# Processor.net
KiCad netlist of a schematic drawn in Altium Designer
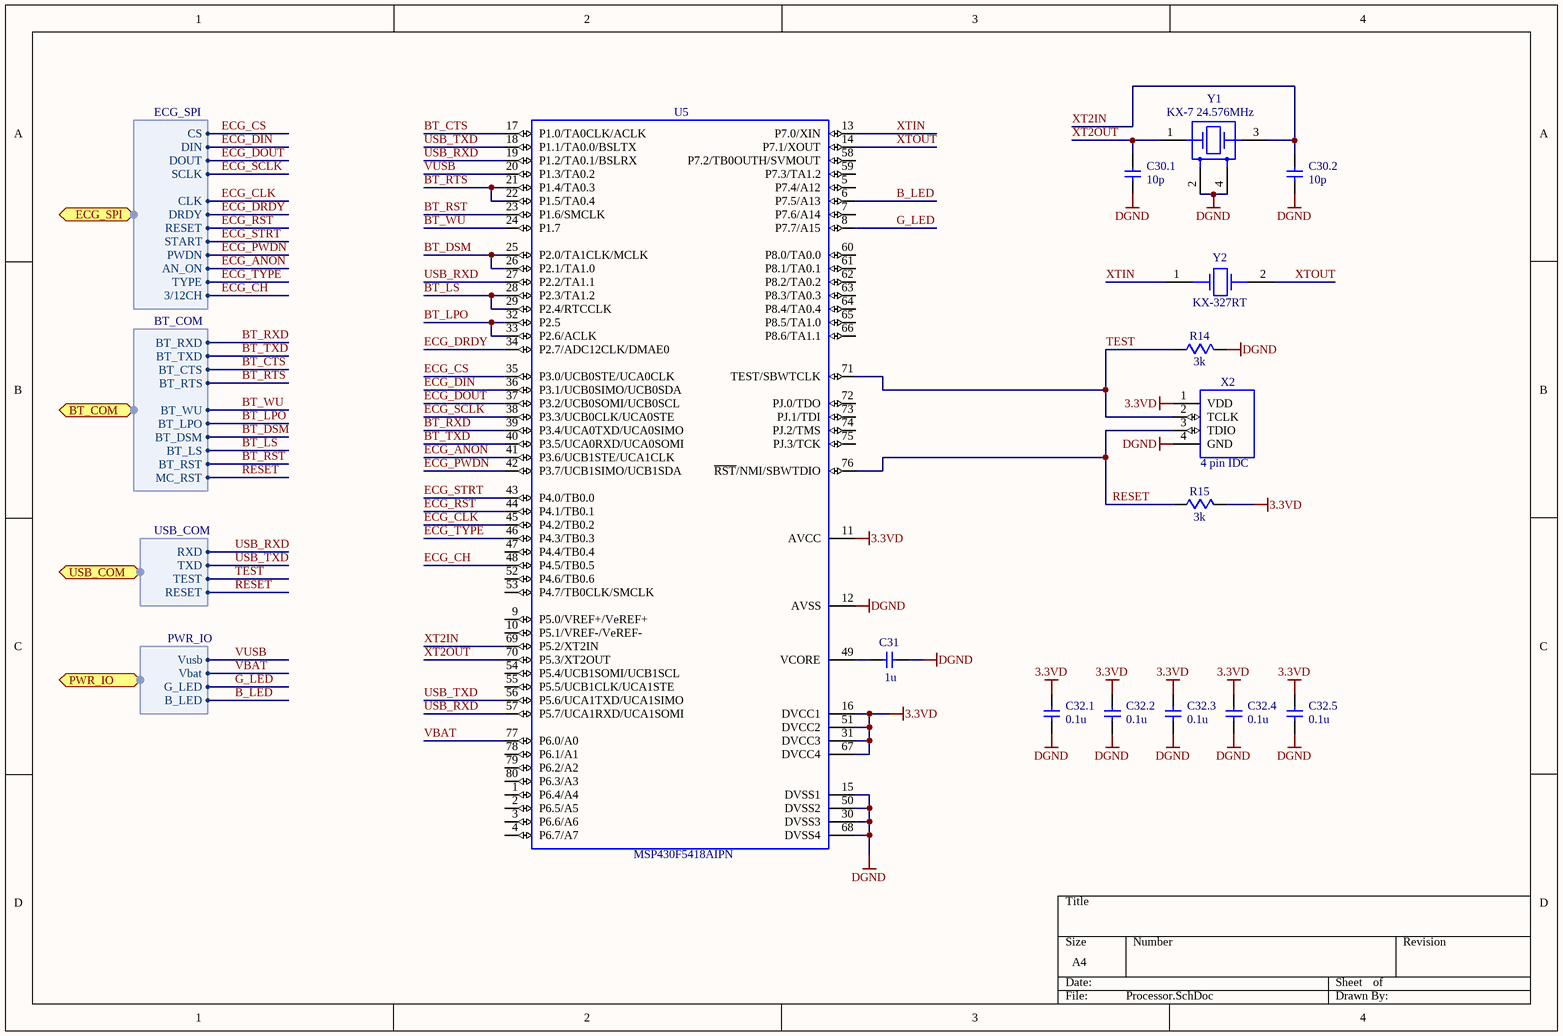
[diagram p0: Processor.SchDoc]

(export (version "E")
  (design (tool "Eeschema 10.0.6"))
  (components
    (comp (ref "C30.1") (value "10p") (footprint "SMD/C/0603") (libsource (lib "My_lib") (part "Capacitor")))
    (comp (ref "C30.2") (value "10p") (footprint "SMD/C/0603") (libsource (lib "My_lib") (part "Capacitor")))
    (comp (ref "C31") (value "1u") (footprint "SMD/C/0603") (libsource (lib "My_lib") (part "Capacitor")))
    (comp (ref "C32.1") (value "0.1u") (footprint "SMD/C/0603") (libsource (lib "My_lib") (part "Capacitor")))
    (comp (ref "C32.2") (value "0.1u") (footprint "SMD/C/0603") (libsource (lib "My_lib") (part "Capacitor")))
    (comp (ref "C32.3") (value "0.1u") (footprint "SMD/C/0603") (libsource (lib "My_lib") (part "Capacitor")))
    (comp (ref "C32.4") (value "0.1u") (footprint "SMD/C/0603") (libsource (lib "My_lib") (part "Capacitor")))
    (comp (ref "C32.5") (value "0.1u") (footprint "SMD/C/0603") (libsource (lib "My_lib") (part "Capacitor")))
    (comp (ref "R14") (value "3k") (footprint "SMD/R/0603") (libsource (lib "My_lib") (part "Resistor")))
    (comp (ref "R15") (value "3k") (footprint "SMD/R/0603") (libsource (lib "My_lib") (part "Resistor")))
    (comp (ref "U5")
      (value "MSP430F5418AIPN")
      (footprint "SMD/QFP80/0.5MMP/12x12MM/14X14MMWP")
      (description "Mixed Signal Microcontroller")
      (libsource (lib "My_lib") (part "MSP430F5418AIPN"))
    )
    (comp (ref "X2")
      (value "4 pin IDC")
      (footprint "CONNECTOR/IDC/0.05P/1X4")
      (description "MSP430 JTAG Connector")
      (libsource (lib "My_lib") (part "MSP430 JTAG SBW"))
    )
    (comp (ref "Y1")
      (value "KX-7 24.576MHz")
      (footprint "KX-7")
      (description "Quartz Crystal")
      (libsource (lib "My_lib") (part "KX-9A"))
    )
    (comp (ref "Y2")
      (value "KX-327RT")
      (footprint "KX–327RT")
      (description "Quartz Crystal")
      (libsource (lib "My_lib") (part "KX-327RT"))
    )
  )
  (nets
    (net (code "5") (name "/BT_CTS") (class "Default")
      (node (ref "U5") (pin "17") (pinfunction "P1.0/TA0CLK/ACLK_17") (pintype "bidirectional"))
    )
    (net (code "6") (name "/BT_DSM") (class "Default")
      (node (ref "U5") (pin "25") (pinfunction "P2.0/TA1CLK/MCLK_25") (pintype "bidirectional"))
      (node (ref "U5") (pin "26") (pinfunction "P2.1/TA1.0_26") (pintype "bidirectional"))
    )
    (net (code "7") (name "/BT_LPO") (class "Default")
      (node (ref "U5") (pin "32") (pinfunction "P2.5_32") (pintype "bidirectional"))
      (node (ref "U5") (pin "33") (pinfunction "P2.6/ACLK_33") (pintype "bidirectional"))
    )
    (net (code "8") (name "/BT_LS") (class "Default")
      (node (ref "U5") (pin "28") (pinfunction "P2.3/TA1.2_28") (pintype "bidirectional"))
      (node (ref "U5") (pin "29") (pinfunction "P2.4/RTCCLK_29") (pintype "bidirectional"))
    )
    (net (code "9") (name "/BT_RST") (class "Default")
      (node (ref "U5") (pin "23") (pinfunction "P1.6/SMCLK_23") (pintype "bidirectional"))
    )
    (net (code "10") (name "/BT_RTS") (class "Default")
      (node (ref "U5") (pin "21") (pinfunction "P1.4/TA0.3_21") (pintype "bidirectional"))
      (node (ref "U5") (pin "22") (pinfunction "P1.5/TA0.4_22") (pintype "bidirectional"))
    )
    (net (code "11") (name "/BT_RXD") (class "Default")
      (node (ref "U5") (pin "39") (pinfunction "P3.4/UCA0TXD/UCA0SIMO_39") (pintype "bidirectional"))
    )
    (net (code "12") (name "/BT_TXD") (class "Default")
      (node (ref "U5") (pin "40") (pinfunction "P3.5/UCA0RXD/UCA0SOMI_40") (pintype "bidirectional"))
    )
    (net (code "13") (name "/BT_WU") (class "Default")
      (node (ref "U5") (pin "24") (pinfunction "P1.7_24") (pintype "bidirectional"))
    )
    (net (code "14") (name "/B_LED") (class "Default")
      (node (ref "U5") (pin "6") (pinfunction "P7.5/A13_6") (pintype "bidirectional"))
    )
    (net (code "15") (name "/ECG_ANON") (class "Default")
      (node (ref "U5") (pin "41") (pinfunction "P3.6/UCB1STE/UCA1CLK_41") (pintype "bidirectional"))
    )
    (net (code "16") (name "/ECG_CH") (class "Default")
      (node (ref "U5") (pin "48") (pinfunction "P4.5/TB0.5_48") (pintype "bidirectional"))
    )
    (net (code "17") (name "/ECG_CLK") (class "Default")
      (node (ref "U5") (pin "45") (pinfunction "P4.2/TB0.2_45") (pintype "bidirectional"))
    )
    (net (code "18") (name "/ECG_CS") (class "Default")
      (node (ref "U5") (pin "35") (pinfunction "P3.0/UCB0STE/UCA0CLK_35") (pintype "bidirectional"))
    )
    (net (code "19") (name "/ECG_DIN") (class "Default")
      (node (ref "U5") (pin "36") (pinfunction "P3.1/UCB0SIMO/UCB0SDA_36") (pintype "bidirectional"))
    )
    (net (code "20") (name "/ECG_DOUT") (class "Default")
      (node (ref "U5") (pin "37") (pinfunction "P3.2/UCB0SOMI/UCB0SCL_37") (pintype "bidirectional"))
    )
    (net (code "21") (name "/ECG_DRDY") (class "Default")
      (node (ref "U5") (pin "34") (pinfunction "P2.7/ADC12CLK/DMAE0_34") (pintype "bidirectional"))
    )
    (net (code "22") (name "/ECG_PWDN") (class "Default")
      (node (ref "U5") (pin "42") (pinfunction "P3.7/UCB1SIMO/UCB1SDA_42") (pintype "bidirectional"))
    )
    (net (code "23") (name "/ECG_RST") (class "Default")
      (node (ref "U5") (pin "44") (pinfunction "P4.1/TB0.1_44") (pintype "bidirectional"))
    )
    (net (code "24") (name "/ECG_SCLK") (class "Default")
      (node (ref "U5") (pin "38") (pinfunction "P3.3/UCB0CLK/UCA0STE_38") (pintype "bidirectional"))
    )
    (net (code "25") (name "/ECG_STRT") (class "Default")
      (node (ref "U5") (pin "43") (pinfunction "P4.0/TB0.0_43") (pintype "bidirectional"))
    )
    (net (code "26") (name "/ECG_TYPE") (class "Default")
      (node (ref "U5") (pin "46") (pinfunction "P4.3/TB0.3_46") (pintype "bidirectional"))
    )
    (net (code "27") (name "/G_LED") (class "Default")
      (node (ref "U5") (pin "8") (pinfunction "P7.7/A15_8") (pintype "bidirectional"))
    )
    (net (code "28") (name "/RESET") (class "Default")
      (node (ref "R15") (pin "1") (pinfunction "1_1") (pintype "passive"))
      (node (ref "U5") (pin "76") (pinfunction "~{RST}/NMI/SBWTDIO_76") (pintype "bidirectional"))
      (node (ref "X2") (pin "3") (pinfunction "TDIO_3") (pintype "bidirectional"))
    )
    (net (code "29") (name "/TEST") (class "Default")
      (node (ref "R14") (pin "1") (pinfunction "1_1") (pintype "passive"))
      (node (ref "U5") (pin "71") (pinfunction "TEST/SBWTCLK_71") (pintype "bidirectional"))
      (node (ref "X2") (pin "2") (pinfunction "TCLK_2") (pintype "bidirectional"))
    )
    (net (code "30") (name "/USB_RXD") (class "Default")
      (node (ref "U5") (pin "19") (pinfunction "P1.2/TA0.1/BSLRX_19") (pintype "bidirectional"))
      (node (ref "U5") (pin "27") (pinfunction "P2.2/TA1.1_27") (pintype "bidirectional"))
      (node (ref "U5") (pin "57") (pinfunction "P5.7/UCA1RXD/UCA1SOMI_57") (pintype "bidirectional"))
    )
    (net (code "31") (name "/USB_TXD") (class "Default")
      (node (ref "U5") (pin "18") (pinfunction "P1.1/TA0.0/BSLTX_18") (pintype "bidirectional"))
      (node (ref "U5") (pin "56") (pinfunction "P5.6/UCA1TXD/UCA1SIMO_56") (pintype "bidirectional"))
    )
    (net (code "32") (name "/VBAT") (class "Default")
      (node (ref "U5") (pin "77") (pinfunction "P6.0/A0_77") (pintype "bidirectional"))
    )
    (net (code "33") (name "/VUSB") (class "Default")
      (node (ref "U5") (pin "20") (pinfunction "P1.3/TA0.2_20") (pintype "bidirectional"))
    )
    (net (code "34") (name "/XT2IN") (class "Default")
      (node (ref "C30.2") (pin "2") (pinfunction "2_2") (pintype "passive"))
      (node (ref "U5") (pin "69") (pinfunction "P5.2/XT2IN_69") (pintype "bidirectional"))
      (node (ref "Y1") (pin "3") (pinfunction "3_3") (pintype "passive"))
    )
    (net (code "35") (name "/XT2OUT") (class "Default")
      (node (ref "C30.1") (pin "2") (pinfunction "2_2") (pintype "passive"))
      (node (ref "U5") (pin "70") (pinfunction "P5.3/XT2OUT_70") (pintype "bidirectional"))
      (node (ref "Y1") (pin "1") (pinfunction "1_1") (pintype "passive"))
    )
    (net (code "36") (name "/XTIN") (class "Default")
      (node (ref "U5") (pin "13") (pinfunction "P7.0/XIN_13") (pintype "bidirectional"))
      (node (ref "Y2") (pin "1") (pinfunction "1_1") (pintype "passive"))
    )
    (net (code "37") (name "/XTOUT") (class "Default")
      (node (ref "U5") (pin "14") (pinfunction "P7.1/XOUT_14") (pintype "bidirectional"))
      (node (ref "Y2") (pin "2") (pinfunction "2_2") (pintype "passive"))
    )
    (net (code "42") (name "3.3VD") (class "Default")
      (node (ref "C32.1") (pin "2") (pinfunction "2_2") (pintype "passive"))
      (node (ref "C32.2") (pin "2") (pinfunction "2_2") (pintype "passive"))
      (node (ref "C32.3") (pin "2") (pinfunction "2_2") (pintype "passive"))
      (node (ref "C32.4") (pin "2") (pinfunction "2_2") (pintype "passive"))
      (node (ref "C32.5") (pin "2") (pinfunction "2_2") (pintype "passive"))
      (node (ref "R15") (pin "2") (pinfunction "2_2") (pintype "passive"))
      (node (ref "U5") (pin "11") (pinfunction "AVCC_11") (pintype "power_in"))
      (node (ref "U5") (pin "16") (pinfunction "DVCC1_16") (pintype "power_in"))
      (node (ref "U5") (pin "31") (pinfunction "DVCC3_31") (pintype "power_in"))
      (node (ref "U5") (pin "51") (pinfunction "DVCC2_51") (pintype "power_in"))
      (node (ref "U5") (pin "67") (pinfunction "DVCC4_67") (pintype "power_in"))
      (node (ref "X2") (pin "1") (pinfunction "VDD_1") (pintype "power_in"))
    )
    (net (code "43") (name "DGND") (class "Default")
      (node (ref "C30.1") (pin "1") (pinfunction "1_1") (pintype "passive"))
      (node (ref "C30.2") (pin "1") (pinfunction "1_1") (pintype "passive"))
      (node (ref "C31") (pin "1") (pinfunction "1_1") (pintype "passive"))
      (node (ref "C32.1") (pin "1") (pinfunction "1_1") (pintype "passive"))
      (node (ref "C32.2") (pin "1") (pinfunction "1_1") (pintype "passive"))
      (node (ref "C32.3") (pin "1") (pinfunction "1_1") (pintype "passive"))
      (node (ref "C32.4") (pin "1") (pinfunction "1_1") (pintype "passive"))
      (node (ref "C32.5") (pin "1") (pinfunction "1_1") (pintype "passive"))
      (node (ref "R14") (pin "2") (pinfunction "2_2") (pintype "passive"))
      (node (ref "U5") (pin "12") (pinfunction "AVSS_12") (pintype "power_in"))
      (node (ref "U5") (pin "15") (pinfunction "DVSS1_15") (pintype "power_in"))
      (node (ref "U5") (pin "30") (pinfunction "DVSS3_30") (pintype "power_in"))
      (node (ref "U5") (pin "50") (pinfunction "DVSS2_50") (pintype "power_in"))
      (node (ref "U5") (pin "68") (pinfunction "DVSS4_68") (pintype "power_in"))
      (node (ref "X2") (pin "4") (pinfunction "GND_4") (pintype "power_in"))
      (node (ref "Y1") (pin "2") (pinfunction "2_2") (pintype "passive"))
      (node (ref "Y1") (pin "4") (pinfunction "4_4") (pintype "passive"))
    )
    (net (code "44") (name "Net-(U5-VCORE)") (class "Default")
      (node (ref "C31") (pin "2") (pinfunction "2_2") (pintype "passive"))
      (node (ref "U5") (pin "49") (pinfunction "VCORE_49") (pintype "power_in"))
    )
    (net (code "45") (name "unconnected-(U5-P4.4{slash}TB0.4-Pad47)") (class "Default")
      (node (ref "U5") (pin "47") (pinfunction "P4.4/TB0.4_47") (pintype "bidirectional"))
    )
    (net (code "46") (name "unconnected-(U5-P4.6{slash}TB0.6-Pad52)") (class "Default")
      (node (ref "U5") (pin "52") (pinfunction "P4.6/TB0.6_52") (pintype "bidirectional"))
    )
    (net (code "47") (name "unconnected-(U5-P4.7{slash}TB0CLK{slash}SMCLK-Pad53)") (class "Default")
      (node (ref "U5") (pin "53") (pinfunction "P4.7/TB0CLK/SMCLK_53") (pintype "bidirectional"))
    )
    (net (code "48") (name "unconnected-(U5-P5.0{slash}VREF+{slash}VeREF+-Pad9)") (class "Default")
      (node (ref "U5") (pin "9") (pinfunction "P5.0/VREF+/VeREF+_9") (pintype "bidirectional"))
    )
    (net (code "49") (name "unconnected-(U5-P5.1{slash}VREF-{slash}VeREF--Pad10)") (class "Default")
      (node (ref "U5") (pin "10") (pinfunction "P5.1/VREF-/VeREF-_10") (pintype "bidirectional"))
    )
    (net (code "50") (name "unconnected-(U5-P5.4{slash}UCB1SOMI{slash}UCB1SCL-Pad54)") (class "Default")
      (node (ref "U5") (pin "54") (pinfunction "P5.4/UCB1SOMI/UCB1SCL_54") (pintype "bidirectional"))
    )
    (net (code "51") (name "unconnected-(U5-P5.5{slash}UCB1CLK{slash}UCA1STE-Pad55)") (class "Default")
      (node (ref "U5") (pin "55") (pinfunction "P5.5/UCB1CLK/UCA1STE_55") (pintype "bidirectional"))
    )
    (net (code "52") (name "unconnected-(U5-P6.1{slash}A1-Pad78)") (class "Default")
      (node (ref "U5") (pin "78") (pinfunction "P6.1/A1_78") (pintype "bidirectional"))
    )
    (net (code "53") (name "unconnected-(U5-P6.2{slash}A2-Pad79)") (class "Default")
      (node (ref "U5") (pin "79") (pinfunction "P6.2/A2_79") (pintype "bidirectional"))
    )
    (net (code "54") (name "unconnected-(U5-P6.3{slash}A3-Pad80)") (class "Default")
      (node (ref "U5") (pin "80") (pinfunction "P6.3/A3_80") (pintype "bidirectional"))
    )
    (net (code "55") (name "unconnected-(U5-P6.4{slash}A4-Pad1)") (class "Default")
      (node (ref "U5") (pin "1") (pinfunction "P6.4/A4_1") (pintype "bidirectional"))
    )
    (net (code "56") (name "unconnected-(U5-P6.5{slash}A5-Pad2)") (class "Default")
      (node (ref "U5") (pin "2") (pinfunction "P6.5/A5_2") (pintype "bidirectional"))
    )
    (net (code "57") (name "unconnected-(U5-P6.6{slash}A6-Pad3)") (class "Default")
      (node (ref "U5") (pin "3") (pinfunction "P6.6/A6_3") (pintype "bidirectional"))
    )
    (net (code "58") (name "unconnected-(U5-P6.7{slash}A7-Pad4)") (class "Default")
      (node (ref "U5") (pin "4") (pinfunction "P6.7/A7_4") (pintype "bidirectional"))
    )
    (net (code "59") (name "unconnected-(U5-P7.2{slash}TB0OUTH{slash}SVMOUT-Pad58)") (class "Default")
      (node (ref "U5") (pin "58") (pinfunction "P7.2/TB0OUTH/SVMOUT_58") (pintype "bidirectional"))
    )
    (net (code "60") (name "unconnected-(U5-P7.3{slash}TA1.2-Pad59)") (class "Default")
      (node (ref "U5") (pin "59") (pinfunction "P7.3/TA1.2_59") (pintype "bidirectional"))
    )
    (net (code "61") (name "unconnected-(U5-P7.4{slash}A12-Pad5)") (class "Default")
      (node (ref "U5") (pin "5") (pinfunction "P7.4/A12_5") (pintype "bidirectional"))
    )
    (net (code "62") (name "unconnected-(U5-P7.6{slash}A14-Pad7)") (class "Default")
      (node (ref "U5") (pin "7") (pinfunction "P7.6/A14_7") (pintype "bidirectional"))
    )
    (net (code "63") (name "unconnected-(U5-P8.0{slash}TA0.0-Pad60)") (class "Default")
      (node (ref "U5") (pin "60") (pinfunction "P8.0/TA0.0_60") (pintype "bidirectional"))
    )
    (net (code "64") (name "unconnected-(U5-P8.1{slash}TA0.1-Pad61)") (class "Default")
      (node (ref "U5") (pin "61") (pinfunction "P8.1/TA0.1_61") (pintype "bidirectional"))
    )
    (net (code "65") (name "unconnected-(U5-P8.2{slash}TA0.2-Pad62)") (class "Default")
      (node (ref "U5") (pin "62") (pinfunction "P8.2/TA0.2_62") (pintype "bidirectional"))
    )
    (net (code "66") (name "unconnected-(U5-P8.3{slash}TA0.3-Pad63)") (class "Default")
      (node (ref "U5") (pin "63") (pinfunction "P8.3/TA0.3_63") (pintype "bidirectional"))
    )
    (net (code "67") (name "unconnected-(U5-P8.4{slash}TA0.4-Pad64)") (class "Default")
      (node (ref "U5") (pin "64") (pinfunction "P8.4/TA0.4_64") (pintype "bidirectional"))
    )
    (net (code "68") (name "unconnected-(U5-P8.5{slash}TA1.0-Pad65)") (class "Default")
      (node (ref "U5") (pin "65") (pinfunction "P8.5/TA1.0_65") (pintype "bidirectional"))
    )
    (net (code "69") (name "unconnected-(U5-P8.6{slash}TA1.1-Pad66)") (class "Default")
      (node (ref "U5") (pin "66") (pinfunction "P8.6/TA1.1_66") (pintype "bidirectional"))
    )
    (net (code "70") (name "unconnected-(U5-PJ.0{slash}TDO-Pad72)") (class "Default")
      (node (ref "U5") (pin "72") (pinfunction "PJ.0/TDO_72") (pintype "bidirectional"))
    )
    (net (code "71") (name "unconnected-(U5-PJ.1{slash}TDI-Pad73)") (class "Default")
      (node (ref "U5") (pin "73") (pinfunction "PJ.1/TDI_73") (pintype "bidirectional"))
    )
    (net (code "72") (name "unconnected-(U5-PJ.2{slash}TMS-Pad74)") (class "Default")
      (node (ref "U5") (pin "74") (pinfunction "PJ.2/TMS_74") (pintype "bidirectional"))
    )
    (net (code "73") (name "unconnected-(U5-PJ.3{slash}TCK-Pad75)") (class "Default")
      (node (ref "U5") (pin "75") (pinfunction "PJ.3/TCK_75") (pintype "bidirectional"))
    )
  )
)
